# OHS.net
KiCad netlist of a schematic drawn in EAGLE
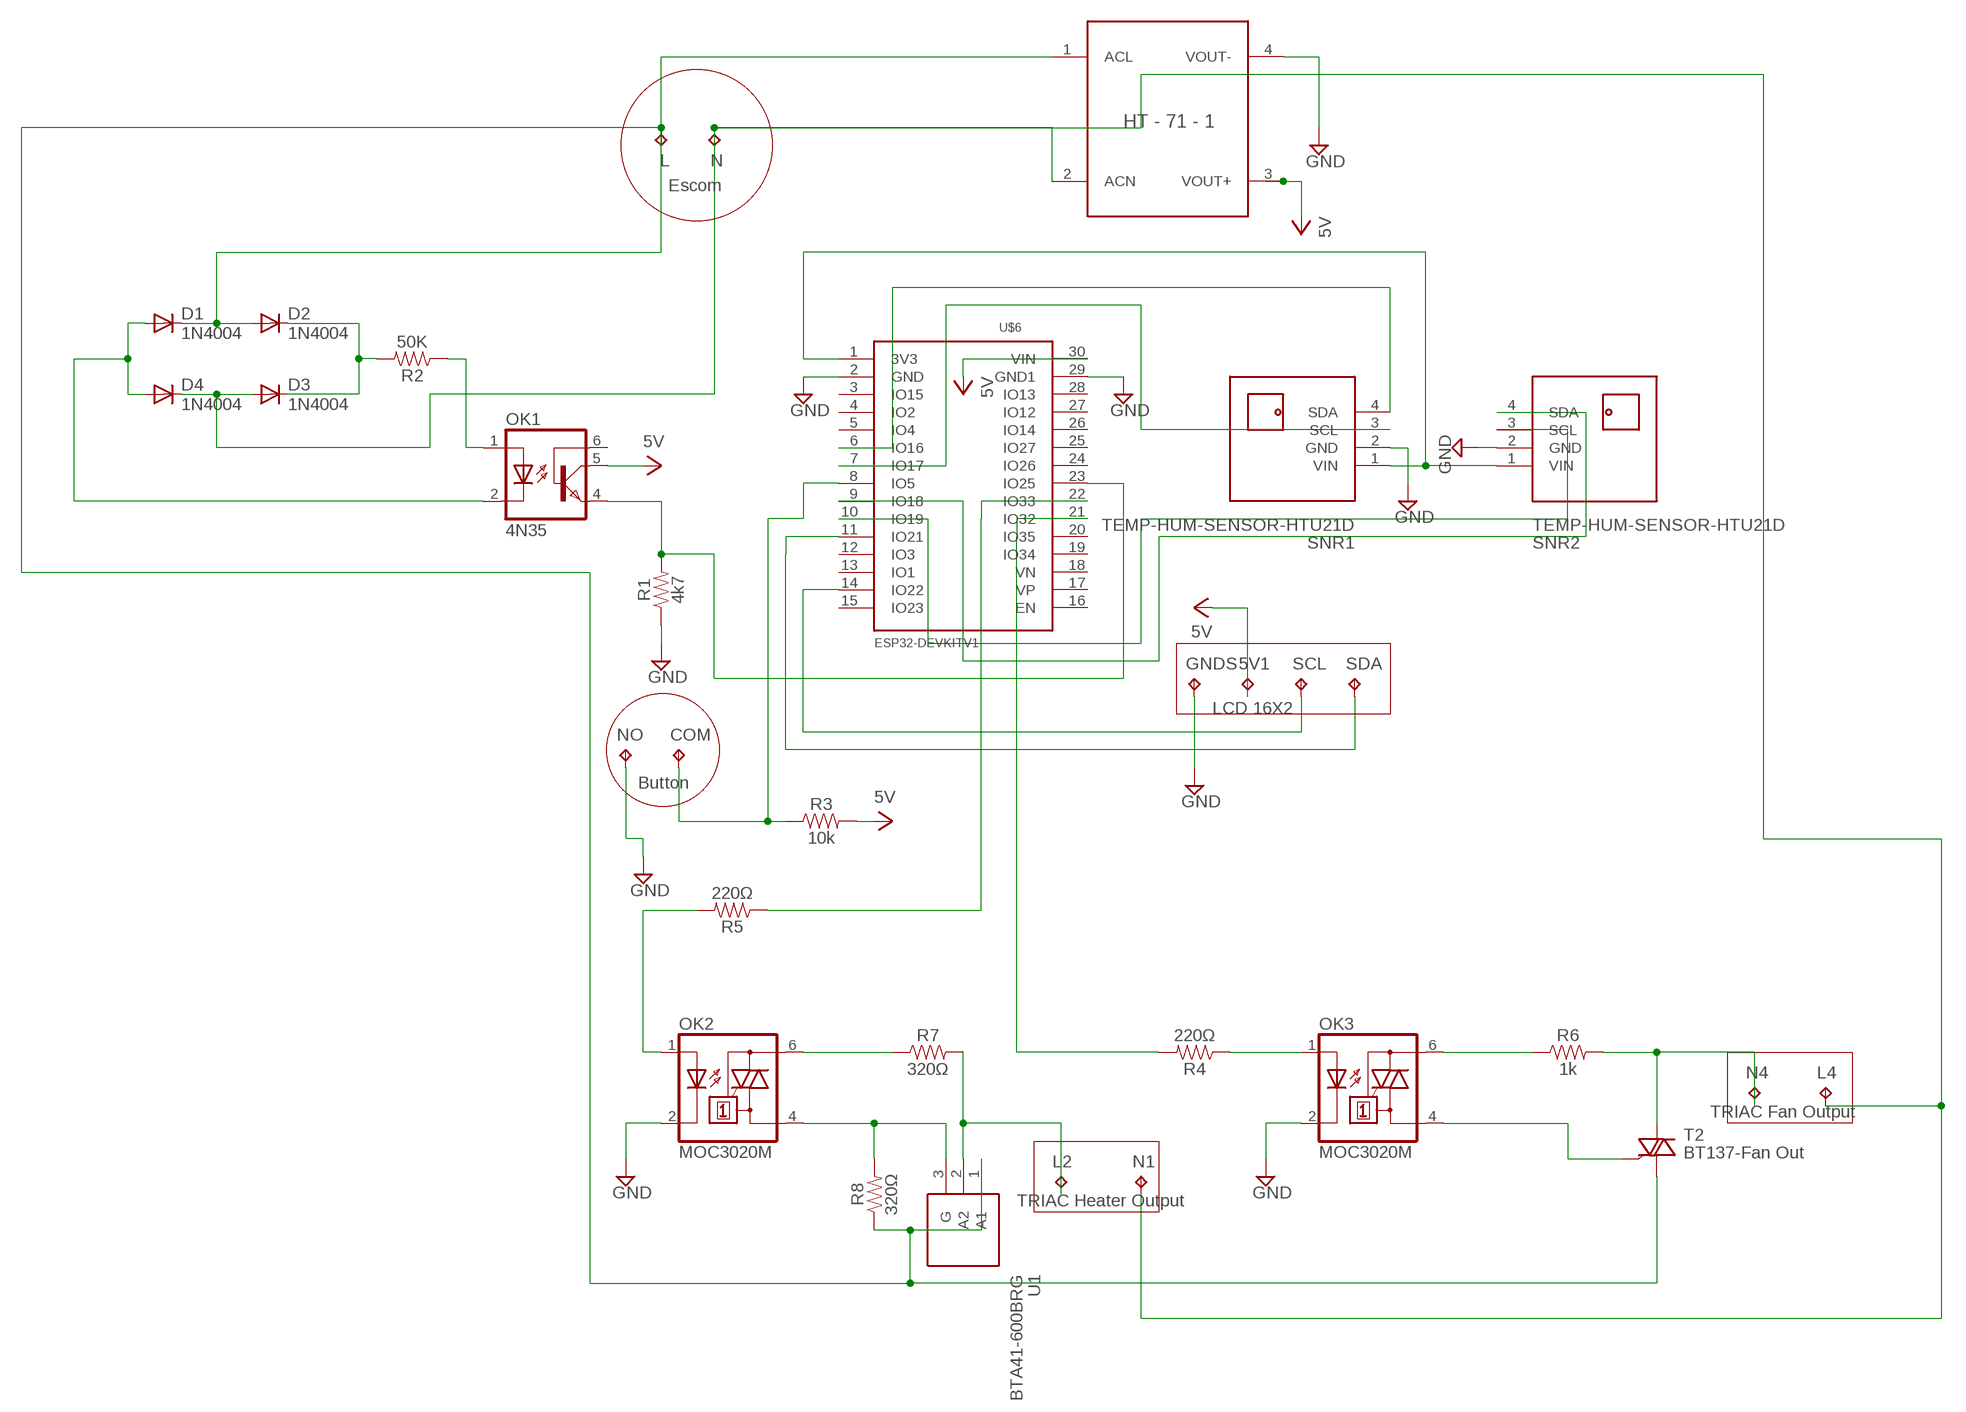
[diagram p0: schematic, sheet 1]

(export (version "E")
  (design (tool "Eeschema 10.0.6"))
  (components
    (comp (ref "5V1")
      (value "TPPAD1-20Y")
      (footprint "eagle-import:P1-20Y")
      (libsource (lib "eagle-import") (part "TPPAD1-20Y"))
    )
    (comp (ref "COM")
      (value "TPPAD1-20Y")
      (footprint "eagle-import:P1-20Y")
      (libsource (lib "eagle-import") (part "TPPAD1-20Y"))
    )
    (comp (ref "D1")
      (value "1N4004")
      (footprint "eagle-import:DO41-10")
      (libsource (lib "eagle-import") (part "1N4004"))
    )
    (comp (ref "D2")
      (value "1N4004")
      (footprint "eagle-import:DO41-10")
      (libsource (lib "eagle-import") (part "1N4004"))
    )
    (comp (ref "D3")
      (value "1N4004")
      (footprint "eagle-import:DO41-10")
      (libsource (lib "eagle-import") (part "1N4004"))
    )
    (comp (ref "D4")
      (value "1N4004")
      (footprint "eagle-import:DO41-10")
      (libsource (lib "eagle-import") (part "1N4004"))
    )
    (comp (ref "GNDS")
      (value "TPPAD1-20Y")
      (footprint "eagle-import:P1-20Y")
      (libsource (lib "eagle-import") (part "TPPAD1-20Y"))
    )
    (comp (ref "L")
      (value "TPPAD1-20Y")
      (footprint "eagle-import:P1-20Y")
      (libsource (lib "eagle-import") (part "TPPAD1-20Y"))
    )
    (comp (ref "L2")
      (value "TPPAD1-20Y")
      (footprint "eagle-import:P1-20Y")
      (libsource (lib "eagle-import") (part "TPPAD1-20Y"))
    )
    (comp (ref "L4")
      (value "TPPAD1-20Y")
      (footprint "eagle-import:P1-20Y")
      (libsource (lib "eagle-import") (part "TPPAD1-20Y"))
    )
    (comp (ref "N")
      (value "TPPAD1-20Y")
      (footprint "eagle-import:P1-20Y")
      (libsource (lib "eagle-import") (part "TPPAD1-20Y"))
    )
    (comp (ref "N1")
      (value "TPPAD1-20Y")
      (footprint "eagle-import:P1-20Y")
      (libsource (lib "eagle-import") (part "TPPAD1-20Y"))
    )
    (comp (ref "N4")
      (value "TPPAD1-20Y")
      (footprint "eagle-import:P1-20Y")
      (libsource (lib "eagle-import") (part "TPPAD1-20Y"))
    )
    (comp (ref "NO")
      (value "TPPAD1-20Y")
      (footprint "eagle-import:P1-20Y")
      (libsource (lib "eagle-import") (part "TPPAD1-20Y"))
    )
    (comp (ref "OK1")
      (value "4N35")
      (footprint "eagle-import:DIL06")
      (fields (field (name "MF") "FAIRCHILD SEMICONDUCTOR"))
      (libsource (lib "eagle-import") (part "4N35"))
    )
    (comp (ref "OK2")
      (value "MOC3020M")
      (footprint "eagle-import:DIL06")
      (fields (field (name "MF") "FAIRCHILD SEMICONDUCTOR") (field (name "MPN") "MOC3020-M"))
      (libsource (lib "eagle-import") (part "MOC30M20"))
    )
    (comp (ref "OK3")
      (value "MOC3020M")
      (footprint "eagle-import:DIL06")
      (fields (field (name "MF") "FAIRCHILD SEMICONDUCTOR") (field (name "MPN") "MOC3020-M"))
      (libsource (lib "eagle-import") (part "MOC30M20"))
    )
    (comp (ref "R1")
      (value "4k7")
      (footprint "eagle-import:AXIAL-0.3")
      (libsource (lib "eagle-import") (part "10KOHM-HORIZ-1/4W-5%"))
    )
    (comp (ref "R2")
      (value "50K")
      (footprint "eagle-import:AXIAL-0.3")
      (libsource (lib "eagle-import") (part "10KOHM-HORIZ-1/4W-5%"))
    )
    (comp (ref "R3")
      (value "10k")
      (footprint "eagle-import:AXIAL-0.3")
      (libsource (lib "eagle-import") (part "10KOHM-HORIZ-1/4W-5%"))
    )
    (comp (ref "R4")
      (value "220Ω")
      (footprint "eagle-import:AXIAL-0.3")
      (libsource (lib "eagle-import") (part "1KOHM-HORIZ-1/4W-5%"))
    )
    (comp (ref "R5")
      (value "220Ω")
      (footprint "eagle-import:AXIAL-0.3")
      (libsource (lib "eagle-import") (part "1KOHM-HORIZ-1/4W-5%"))
    )
    (comp (ref "R6")
      (value "1k")
      (footprint "eagle-import:AXIAL-0.3")
      (libsource (lib "eagle-import") (part "1KOHM-HORIZ-1/4W-5%"))
    )
    (comp (ref "R7")
      (value "320Ω")
      (footprint "eagle-import:AXIAL-0.3")
      (libsource (lib "eagle-import") (part "1KOHM-HORIZ-1/4W-5%"))
    )
    (comp (ref "R8")
      (value "320Ω")
      (footprint "eagle-import:AXIAL-0.3")
      (libsource (lib "eagle-import") (part "1KOHM-HORIZ-1/4W-5%"))
    )
    (comp (ref "SCL")
      (value "TPPAD1-20Y")
      (footprint "eagle-import:P1-20Y")
      (libsource (lib "eagle-import") (part "TPPAD1-20Y"))
    )
    (comp (ref "SDA")
      (value "TPPAD1-20Y")
      (footprint "eagle-import:P1-20Y")
      (libsource (lib "eagle-import") (part "TPPAD1-20Y"))
    )
    (comp (ref "SNR1")
      (value "TEMP-HUM-SENSOR-HTU21D")
      (footprint "eagle-import:TEMP-HUM-SENSOR-HTU21D")
      (libsource (lib "eagle-import") (part "TEMP-HUM-SENSOR-HTU21D"))
    )
    (comp (ref "SNR2")
      (value "TEMP-HUM-SENSOR-HTU21D")
      (footprint "eagle-import:TEMP-HUM-SENSOR-HTU21D")
      (libsource (lib "eagle-import") (part "TEMP-HUM-SENSOR-HTU21D"))
    )
    (comp (ref "T2")
      (value "BT137-Fan Out")
      (footprint "eagle-import:TO220BV")
      (libsource (lib "eagle-import") (part "BT138-V"))
    )
    (comp (ref "U$1")
      (value "AD-DC-240-5")
      (footprint "eagle-import:HT-71-1")
      (libsource (lib "eagle-import") (part "AD-DC-240-5"))
    )
    (comp (ref "U$6")
      (value "ESP32DEVKITV1")
      (footprint "eagle-import:ESP32-DEVKITV1")
      (libsource (lib "eagle-import") (part "ESP32DEVKITV1"))
    )
    (comp (ref "U1")
      (value "BTA41-600BRG")
      (footprint "eagle-import:TO552P460X1530X2985-3P")
      (fields (field (name "MOUSER_PART_NUMBER") "511-BTA41-600B") (field (name "RS_PART_NUMBER") "6871007P"))
      (libsource (lib "eagle-import") (part "BTA41-600BRG"))
    )
  )
  (nets
    (net (code "1") (name "5V") (class "Default")
      (node (ref "5V1") (pin "TP") (pinfunction "TP_TP") (pintype "input"))
      (node (ref "OK1") (pin "5") (pinfunction "COL_5") (pintype "passive"))
      (node (ref "R3") (pin "P$2") (pinfunction "2_P$2") (pintype "passive"))
      (node (ref "U$1") (pin "3") (pinfunction "VOUT+_3") (pintype "bidirectional"))
      (node (ref "U$6") (pin "30") (pinfunction "VIN_30") (pintype "bidirectional"))
    )
    (net (code "2") (name "GND") (class "Default")
      (node (ref "GNDS") (pin "TP") (pinfunction "TP_TP") (pintype "input"))
      (node (ref "NO") (pin "TP") (pinfunction "TP_TP") (pintype "input"))
      (node (ref "OK2") (pin "2") (pinfunction "C_2") (pintype "passive"))
      (node (ref "OK3") (pin "2") (pinfunction "C_2") (pintype "passive"))
      (node (ref "R1") (pin "P$1") (pinfunction "1_P$1") (pintype "passive"))
      (node (ref "SNR1") (pin "2") (pinfunction "GND_2") (pintype "power_in"))
      (node (ref "SNR2") (pin "2") (pinfunction "GND_2") (pintype "power_in"))
      (node (ref "U$1") (pin "4") (pinfunction "VOUT-_4") (pintype "bidirectional"))
      (node (ref "U$6") (pin "2") (pinfunction "GND_2") (pintype "bidirectional"))
      (node (ref "U$6") (pin "29") (pinfunction "GND1_29") (pintype "bidirectional"))
    )
    (net (code "3") (name "Net-(OK1-A)") (class "Default")
      (node (ref "OK1") (pin "1") (pinfunction "A_1") (pintype "passive"))
      (node (ref "R2") (pin "P$1") (pinfunction "1_P$1") (pintype "passive"))
    )
    (net (code "4") (name "Net-(OK1-C)") (class "Default")
      (node (ref "D1") (pin "A") (pinfunction "A_A") (pintype "passive"))
      (node (ref "D4") (pin "A") (pinfunction "A_A") (pintype "passive"))
      (node (ref "OK1") (pin "2") (pinfunction "C_2") (pintype "passive"))
    )
    (net (code "5") (name "Net-(OK1-EMI)") (class "Default")
      (node (ref "OK1") (pin "4") (pinfunction "EMI_4") (pintype "passive"))
      (node (ref "R1") (pin "P$2") (pinfunction "2_P$2") (pintype "passive"))
      (node (ref "U$6") (pin "23") (pinfunction "IO25_23") (pintype "bidirectional"))
    )
    (net (code "6") (name "Net-(OK2-A)") (class "Default")
      (node (ref "OK2") (pin "1") (pinfunction "A_1") (pintype "passive"))
      (node (ref "R5") (pin "P$2") (pinfunction "2_P$2") (pintype "passive"))
    )
    (net (code "7") (name "Net-(OK2-A1)") (class "Default")
      (node (ref "OK2") (pin "4") (pinfunction "A1_4") (pintype "passive"))
      (node (ref "R8") (pin "P$2") (pinfunction "2_P$2") (pintype "passive"))
      (node (ref "U1") (pin "3") (pinfunction "G_3") (pintype "bidirectional"))
    )
    (net (code "8") (name "Net-(OK2-A2)") (class "Default")
      (node (ref "OK2") (pin "6") (pinfunction "A2_6") (pintype "passive"))
      (node (ref "R7") (pin "P$1") (pinfunction "1_P$1") (pintype "passive"))
    )
    (net (code "9") (name "Net-(OK3-A)") (class "Default")
      (node (ref "OK3") (pin "1") (pinfunction "A_1") (pintype "passive"))
      (node (ref "R4") (pin "P$1") (pinfunction "1_P$1") (pintype "passive"))
    )
    (net (code "10") (name "Net-(OK3-A1)") (class "Default")
      (node (ref "OK3") (pin "4") (pinfunction "A1_4") (pintype "passive"))
      (node (ref "T2") (pin "G") (pinfunction "G_G") (pintype "passive"))
    )
    (net (code "11") (name "Net-(OK3-A2)") (class "Default")
      (node (ref "OK3") (pin "6") (pinfunction "A2_6") (pintype "passive"))
      (node (ref "R6") (pin "P$1") (pinfunction "1_P$1") (pintype "passive"))
    )
    (net (code "12") (name "Net-(R2-2)") (class "Default")
      (node (ref "D2") (pin "C") (pinfunction "C_C") (pintype "passive"))
      (node (ref "D3") (pin "C") (pinfunction "C_C") (pintype "passive"))
      (node (ref "R2") (pin "P$2") (pinfunction "2_P$2") (pintype "passive"))
    )
    (net (code "13") (name "Net-(R3-1)") (class "Default")
      (node (ref "COM") (pin "TP") (pinfunction "TP_TP") (pintype "input"))
      (node (ref "R3") (pin "P$1") (pinfunction "1_P$1") (pintype "passive"))
      (node (ref "U$6") (pin "8") (pinfunction "IO5_8") (pintype "bidirectional"))
    )
    (net (code "14") (name "Net-(R4-2)") (class "Default")
      (node (ref "R4") (pin "P$2") (pinfunction "2_P$2") (pintype "passive"))
      (node (ref "U$6") (pin "21") (pinfunction "IO32_21") (pintype "bidirectional"))
    )
    (net (code "15") (name "Net-(R5-1)") (class "Default")
      (node (ref "R5") (pin "P$1") (pinfunction "1_P$1") (pintype "passive"))
      (node (ref "U$6") (pin "22") (pinfunction "IO33_22") (pintype "bidirectional"))
    )
    (net (code "16") (name "Net-(R6-2)") (class "Default")
      (node (ref "N4") (pin "TP") (pinfunction "TP_TP") (pintype "input"))
      (node (ref "R6") (pin "P$2") (pinfunction "2_P$2") (pintype "passive"))
      (node (ref "T2") (pin "T2") (pinfunction "A2_T2") (pintype "passive"))
    )
    (net (code "17") (name "Net-(R7-2)") (class "Default")
      (node (ref "L2") (pin "TP") (pinfunction "TP_TP") (pintype "input"))
      (node (ref "R7") (pin "P$2") (pinfunction "2_P$2") (pintype "passive"))
      (node (ref "U1") (pin "2") (pinfunction "A2_2") (pintype "bidirectional"))
    )
    (net (code "18") (name "Net-(R8-1)") (class "Default")
      (node (ref "D1") (pin "C") (pinfunction "C_C") (pintype "passive"))
      (node (ref "D2") (pin "A") (pinfunction "A_A") (pintype "passive"))
      (node (ref "L") (pin "TP") (pinfunction "TP_TP") (pintype "input"))
      (node (ref "R8") (pin "P$1") (pinfunction "1_P$1") (pintype "passive"))
      (node (ref "T2") (pin "T1") (pinfunction "A1_T1") (pintype "passive"))
      (node (ref "U$1") (pin "1") (pinfunction "ACL_1") (pintype "bidirectional"))
      (node (ref "U1") (pin "1") (pinfunction "A1_1") (pintype "bidirectional"))
    )
    (net (code "19") (name "Net-(SNR1-SCL)") (class "Default")
      (node (ref "SNR1") (pin "3") (pinfunction "SCL_3") (pintype "bidirectional"))
      (node (ref "U$6") (pin "7") (pinfunction "IO17_7") (pintype "bidirectional"))
    )
    (net (code "20") (name "Net-(SNR1-SDA)") (class "Default")
      (node (ref "SNR1") (pin "4") (pinfunction "SDA_4") (pintype "bidirectional"))
      (node (ref "U$6") (pin "6") (pinfunction "IO16_6") (pintype "bidirectional"))
    )
    (net (code "21") (name "Net-(SNR1-VIN)") (class "Default")
      (node (ref "SNR1") (pin "1") (pinfunction "VIN_1") (pintype "power_in"))
      (node (ref "SNR2") (pin "1") (pinfunction "VIN_1") (pintype "power_in"))
      (node (ref "U$6") (pin "1") (pinfunction "3V3_1") (pintype "bidirectional"))
    )
    (net (code "22") (name "Net-(SNR2-SCL)") (class "Default")
      (node (ref "SNR2") (pin "3") (pinfunction "SCL_3") (pintype "bidirectional"))
      (node (ref "U$6") (pin "10") (pinfunction "IO19_10") (pintype "bidirectional"))
    )
    (net (code "23") (name "Net-(SNR2-SDA)") (class "Default")
      (node (ref "SNR2") (pin "4") (pinfunction "SDA_4") (pintype "bidirectional"))
      (node (ref "U$6") (pin "9") (pinfunction "IO18_9") (pintype "bidirectional"))
    )
    (net (code "24") (name "Net-(U$1-ACN)") (class "Default")
      (node (ref "D3") (pin "A") (pinfunction "A_A") (pintype "passive"))
      (node (ref "D4") (pin "C") (pinfunction "C_C") (pintype "passive"))
      (node (ref "L4") (pin "TP") (pinfunction "TP_TP") (pintype "input"))
      (node (ref "N") (pin "TP") (pinfunction "TP_TP") (pintype "input"))
      (node (ref "N1") (pin "TP") (pinfunction "TP_TP") (pintype "input"))
      (node (ref "U$1") (pin "2") (pinfunction "ACN_2") (pintype "bidirectional"))
    )
    (net (code "25") (name "Net-(U$6-IO21)") (class "Default")
      (node (ref "SDA") (pin "TP") (pinfunction "TP_TP") (pintype "input"))
      (node (ref "U$6") (pin "11") (pinfunction "IO21_11") (pintype "bidirectional"))
    )
    (net (code "26") (name "Net-(U$6-IO22)") (class "Default")
      (node (ref "SCL") (pin "TP") (pinfunction "TP_TP") (pintype "input"))
      (node (ref "U$6") (pin "14") (pinfunction "IO22_14") (pintype "bidirectional"))
    )
    (net (code "27") (name "unconnected-(OK1-BAS-Pad6)") (class "Default")
      (node (ref "OK1") (pin "6") (pinfunction "BAS_6") (pintype "passive"))
    )
    (net (code "28") (name "unconnected-(U$6-EN-Pad16)") (class "Default")
      (node (ref "U$6") (pin "16") (pinfunction "EN_16") (pintype "bidirectional"))
    )
    (net (code "29") (name "unconnected-(U$6-IO1-Pad13)") (class "Default")
      (node (ref "U$6") (pin "13") (pinfunction "IO1_13") (pintype "bidirectional"))
    )
    (net (code "30") (name "unconnected-(U$6-IO2-Pad4)") (class "Default")
      (node (ref "U$6") (pin "4") (pinfunction "IO2_4") (pintype "bidirectional"))
    )
    (net (code "31") (name "unconnected-(U$6-IO3-Pad12)") (class "Default")
      (node (ref "U$6") (pin "12") (pinfunction "IO3_12") (pintype "bidirectional"))
    )
    (net (code "32") (name "unconnected-(U$6-IO4-Pad5)") (class "Default")
      (node (ref "U$6") (pin "5") (pinfunction "IO4_5") (pintype "bidirectional"))
    )
    (net (code "33") (name "unconnected-(U$6-IO12-Pad27)") (class "Default")
      (node (ref "U$6") (pin "27") (pinfunction "IO12_27") (pintype "bidirectional"))
    )
    (net (code "34") (name "unconnected-(U$6-IO13-Pad28)") (class "Default")
      (node (ref "U$6") (pin "28") (pinfunction "IO13_28") (pintype "bidirectional"))
    )
    (net (code "35") (name "unconnected-(U$6-IO14-Pad26)") (class "Default")
      (node (ref "U$6") (pin "26") (pinfunction "IO14_26") (pintype "bidirectional"))
    )
    (net (code "36") (name "unconnected-(U$6-IO15-Pad3)") (class "Default")
      (node (ref "U$6") (pin "3") (pinfunction "IO15_3") (pintype "bidirectional"))
    )
    (net (code "37") (name "unconnected-(U$6-IO23-Pad15)") (class "Default")
      (node (ref "U$6") (pin "15") (pinfunction "IO23_15") (pintype "bidirectional"))
    )
    (net (code "38") (name "unconnected-(U$6-IO26-Pad24)") (class "Default")
      (node (ref "U$6") (pin "24") (pinfunction "IO26_24") (pintype "bidirectional"))
    )
    (net (code "39") (name "unconnected-(U$6-IO27-Pad25)") (class "Default")
      (node (ref "U$6") (pin "25") (pinfunction "IO27_25") (pintype "bidirectional"))
    )
    (net (code "40") (name "unconnected-(U$6-IO34-Pad19)") (class "Default")
      (node (ref "U$6") (pin "19") (pinfunction "IO34_19") (pintype "bidirectional"))
    )
    (net (code "41") (name "unconnected-(U$6-IO35-Pad20)") (class "Default")
      (node (ref "U$6") (pin "20") (pinfunction "IO35_20") (pintype "bidirectional"))
    )
    (net (code "42") (name "unconnected-(U$6-VN-Pad18)") (class "Default")
      (node (ref "U$6") (pin "18") (pinfunction "VN_18") (pintype "bidirectional"))
    )
    (net (code "43") (name "unconnected-(U$6-VP-Pad17)") (class "Default")
      (node (ref "U$6") (pin "17") (pinfunction "VP_17") (pintype "bidirectional"))
    )
  )
)
